# 5vBuckV2.net
KiCad netlist of a schematic drawn in EAGLE
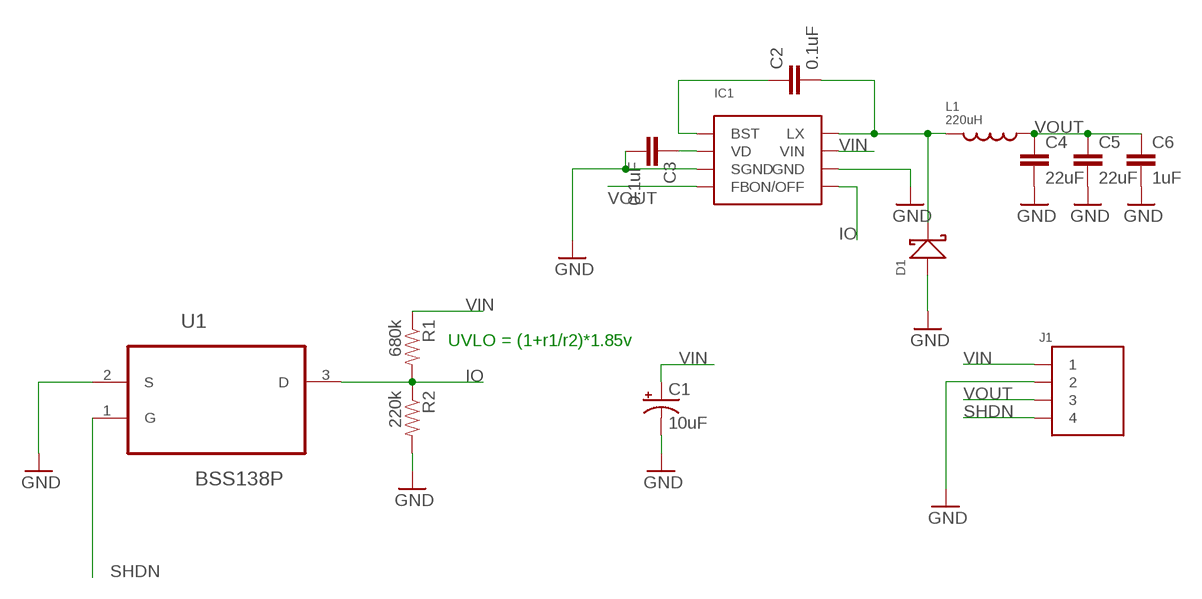
[diagram p0: schematic, sheet 1]

(export (version "E")
  (design (tool "Eeschema 10.0.6"))
  (components
    (comp (ref "C1")
      (value "10uF")
      (footprint "eagle-import:NIPPON_F80")
      (libsource (lib "eagle-import") (part "CAP_POLF80"))
    )
    (comp (ref "C2")
      (value "0.1uF")
      (footprint "eagle-import:0805-CAP")
      (libsource (lib "eagle-import") (part "0.33UF-50V-10%(0805)"))
    )
    (comp (ref "C3")
      (value "0.1uF")
      (footprint "eagle-import:0805-CAP")
      (libsource (lib "eagle-import") (part "0.33UF-50V-10%(0805)"))
    )
    (comp (ref "C4")
      (value "22uF")
      (footprint "eagle-import:0805-CAP")
      (libsource (lib "eagle-import") (part "0.33UF-50V-10%(0805)"))
    )
    (comp (ref "C5")
      (value "22uF")
      (footprint "eagle-import:0805-CAP")
      (libsource (lib "eagle-import") (part "0.33UF-50V-10%(0805)"))
    )
    (comp (ref "C6")
      (value "1uF")
      (footprint "eagle-import:0805-CAP")
      (libsource (lib "eagle-import") (part "0.33UF-50V-10%(0805)"))
    )
    (comp (ref "D1")
      (value "DIODE_SCHOTTKYSOD-123")
      (footprint "eagle-import:SOD-123")
      (libsource (lib "eagle-import") (part "DIODE_SCHOTTKYSOD-123"))
    )
    (comp (ref "IC1")
      (value "M5033")
      (footprint "eagle-import:SOIC-8")
      (libsource (lib "eagle-import") (part "M5033"))
    )
    (comp (ref "J1")
      (value "CONNECTOR_4PIN")
      (footprint "eagle-import:4PIN_.1'")
      (libsource (lib "eagle-import") (part "CONNECTOR_4PIN"))
    )
    (comp (ref "L1")
      (value "220uH")
      (footprint "eagle-import:6X6MM_IND")
      (libsource (lib "eagle-import") (part "CHIP_IND1"))
    )
    (comp (ref "R1")
      (value "680k")
      (footprint "eagle-import:0805")
      (libsource (lib "eagle-import") (part "0.22OHM-1/4W-1%(0805)"))
    )
    (comp (ref "R2")
      (value "220k")
      (footprint "eagle-import:0805")
      (libsource (lib "eagle-import") (part "0.22OHM-1/4W-1%(0805)"))
    )
    (comp (ref "U1")
      (value "BSS138P")
      (footprint "eagle-import:SOT95P230X110-3N")
      (libsource (lib "eagle-import") (part "BSS138P"))
    )
  )
  (nets
    (net (code "1") (name "/IO") (class "Default")
      (node (ref "IC1") (pin "P$5") (pinfunction "ON/OFF_P$5") (pintype "bidirectional"))
      (node (ref "R1") (pin "2") (pinfunction "2_2") (pintype "passive"))
      (node (ref "R2") (pin "1") (pinfunction "1_1") (pintype "passive"))
      (node (ref "U1") (pin "3") (pinfunction "D_3") (pintype "passive"))
    )
    (net (code "2") (name "/SHDN") (class "Default")
      (node (ref "J1") (pin "P$4") (pinfunction "4_P$4") (pintype "bidirectional"))
      (node (ref "U1") (pin "1") (pinfunction "G_1") (pintype "passive"))
    )
    (net (code "3") (name "/VIN") (class "Default")
      (node (ref "C1") (pin "+") (pinfunction "+_+") (pintype "passive"))
      (node (ref "IC1") (pin "P$7") (pinfunction "VIN_P$7") (pintype "bidirectional"))
      (node (ref "J1") (pin "P$1") (pinfunction "1_P$1") (pintype "bidirectional"))
      (node (ref "R1") (pin "1") (pinfunction "1_1") (pintype "passive"))
    )
    (net (code "4") (name "/VOUT") (class "Default")
      (node (ref "C4") (pin "1") (pinfunction "1_1") (pintype "passive"))
      (node (ref "C5") (pin "1") (pinfunction "1_1") (pintype "passive"))
      (node (ref "C6") (pin "1") (pinfunction "1_1") (pintype "passive"))
      (node (ref "IC1") (pin "P$4") (pinfunction "FB_P$4") (pintype "bidirectional"))
      (node (ref "J1") (pin "P$3") (pinfunction "3_P$3") (pintype "bidirectional"))
      (node (ref "L1") (pin "P$2") (pinfunction "P$2_P$2") (pintype "bidirectional"))
    )
    (net (code "5") (name "GND") (class "Default")
      (node (ref "C1") (pin "-") (pinfunction "-_-") (pintype "passive"))
      (node (ref "C3") (pin "2") (pinfunction "2_2") (pintype "passive"))
      (node (ref "C4") (pin "2") (pinfunction "2_2") (pintype "passive"))
      (node (ref "C5") (pin "2") (pinfunction "2_2") (pintype "passive"))
      (node (ref "C6") (pin "2") (pinfunction "2_2") (pintype "passive"))
      (node (ref "D1") (pin "ANODE") (pinfunction "ANODE_ANODE") (pintype "bidirectional"))
      (node (ref "IC1") (pin "P$3") (pinfunction "SGND_P$3") (pintype "bidirectional"))
      (node (ref "IC1") (pin "P$6") (pinfunction "GND_P$6") (pintype "bidirectional"))
      (node (ref "J1") (pin "P$2") (pinfunction "2_P$2") (pintype "bidirectional"))
      (node (ref "R2") (pin "2") (pinfunction "2_2") (pintype "passive"))
      (node (ref "U1") (pin "2") (pinfunction "S_2") (pintype "passive"))
    )
    (net (code "6") (name "Net-(IC1-BST)") (class "Default")
      (node (ref "C2") (pin "1") (pinfunction "1_1") (pintype "passive"))
      (node (ref "IC1") (pin "P$1") (pinfunction "BST_P$1") (pintype "bidirectional"))
    )
    (net (code "7") (name "Net-(IC1-LX)") (class "Default")
      (node (ref "C2") (pin "2") (pinfunction "2_2") (pintype "passive"))
      (node (ref "D1") (pin "CATHODE") (pinfunction "CATHODE_CATHODE") (pintype "bidirectional"))
      (node (ref "IC1") (pin "P$8") (pinfunction "LX_P$8") (pintype "bidirectional"))
      (node (ref "L1") (pin "P$1") (pinfunction "P$1_P$1") (pintype "bidirectional"))
    )
    (net (code "8") (name "Net-(IC1-VD)") (class "Default")
      (node (ref "C3") (pin "1") (pinfunction "1_1") (pintype "passive"))
      (node (ref "IC1") (pin "P$2") (pinfunction "VD_P$2") (pintype "bidirectional"))
    )
  )
)
